# MCU.net
KiCad netlist of a schematic drawn in Altium Designer
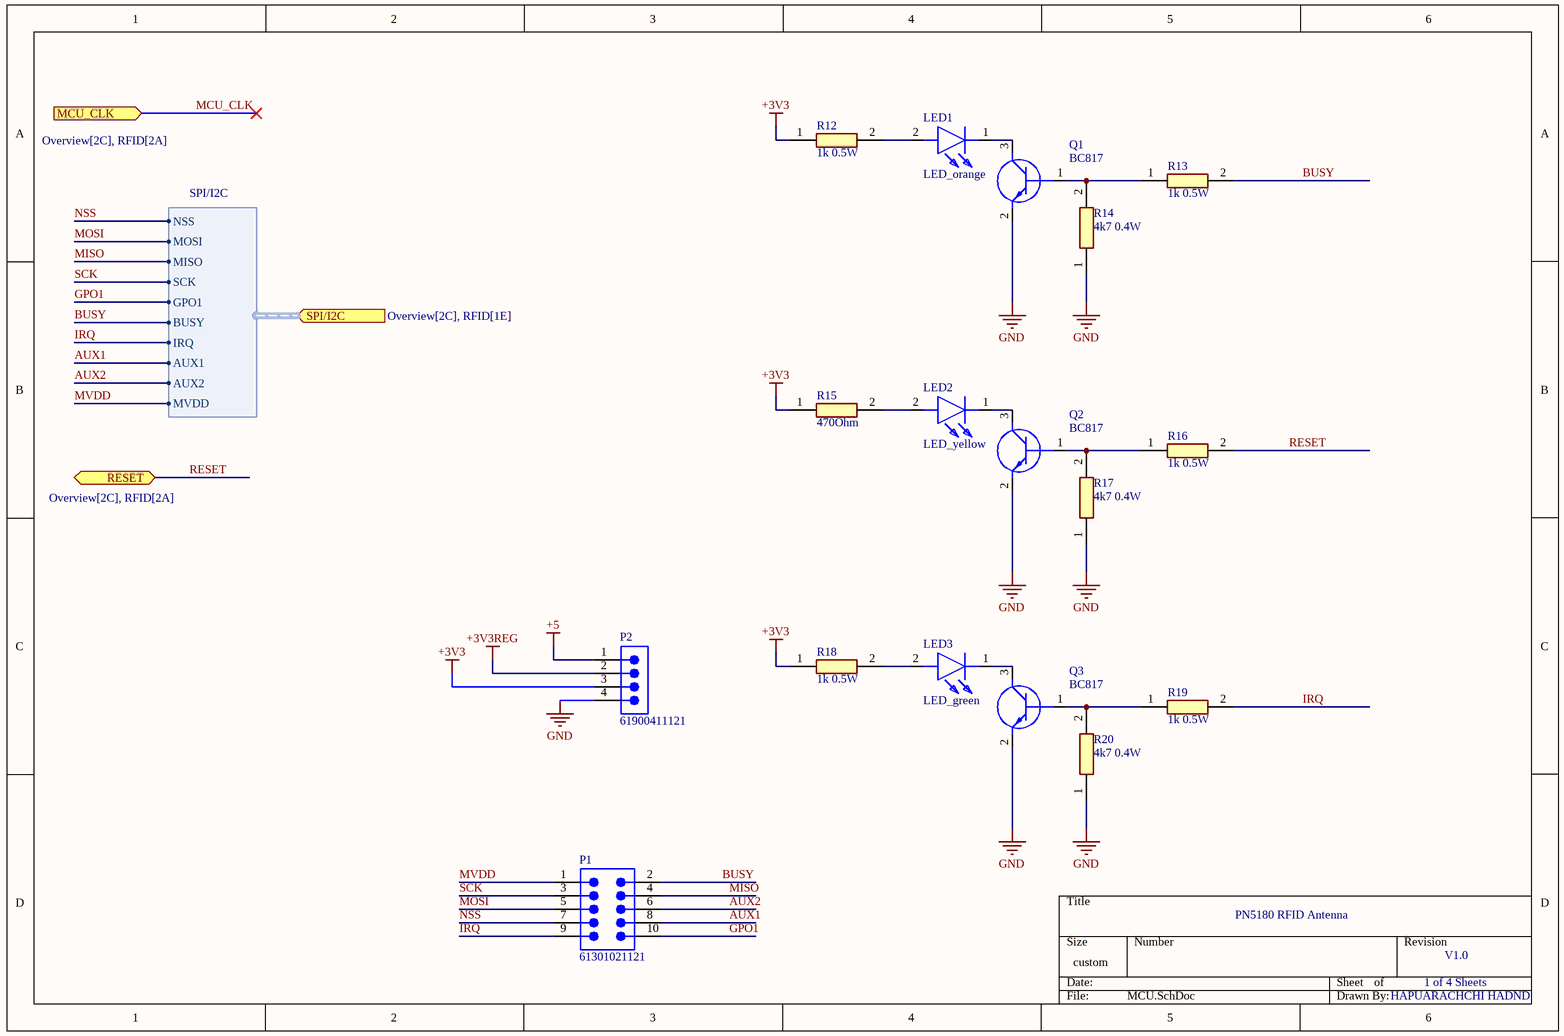
[diagram p0: MCU.SchDoc]

(export (version "E")
  (design (tool "Eeschema 10.0.6"))
  (components
    (comp (ref "LED1")
      (value "LED_orange")
      (footprint "Antenna_Order:LEDC3216X120N")
      (description "LED")
      (fields
        (field (name "MANUFACTURER_PART_NUMBER") "LTST-C150KAKT")
        (field (name "MOUSER PART NUMBER") "859-LTST-C150KAKT")
      )
      (libsource (lib "Antenna_Order") (part "LED_orange"))
    )
    (comp (ref "LED2")
      (value "LED_yellow")
      (footprint "Antenna_Order:LTSTC171KSKT")
      (description "LED")
      (fields
        (field (name "MANUFACTURER_PART_NUMBER") "LTST-C171KSKT")
        (field (name "MOUSER PART NUMBER") "859-LTST-C171KSKT")
      )
      (libsource (lib "Antenna_Order") (part "LED_yellow"))
    )
    (comp (ref "LED3")
      (value "LED_green")
      (footprint "Antenna_Order:LEDC2012X90N")
      (description "LED")
      (fields
        (field (name "MANUFACTURER_PART_NUMBER") "LTST-C171KGKT")
        (field (name "MOUSER PART NUMBER") "859-LTST-C171KGKT")
      )
      (libsource (lib "Antenna_Order") (part "LED_green"))
    )
    (comp (ref "P1")
      (value "61301021121")
      (footprint "61301021121")
      (libsource (lib "Altium Content Vault") (part "Header_Male_2R_10P"))
    )
    (comp (ref "P2")
      (value "61900411121")
      (footprint "61900411121")
      (libsource (lib "Altium Content Vault") (part "Header_Male_1R_04P"))
    )
    (comp (ref "Q1")
      (value "BC817")
      (footprint "Antenna_Order:SOT96P237X111-3N")
      (description "Bipolar (BJT) Transistor NPN 80 V 500 mA 100MHz 225 mW Surface Mount SOT-23-3 (TO-236)")
      (fields
        (field (name "MANUFACTURER_PART_NUMBER") "SMMBTA06LT3G")
        (field (name "MOUSER PART NUMBER") "863-SMMBTA06LT3G")
      )
      (libsource (lib "Antenna_Order") (part "BC817"))
    )
    (comp (ref "Q2")
      (value "BC817")
      (footprint "Antenna_Order:SOT96P237X111-3N")
      (description "Bipolar (BJT) Transistor NPN 80 V 500 mA 100MHz 225 mW Surface Mount SOT-23-3 (TO-236)")
      (fields
        (field (name "MANUFACTURER_PART_NUMBER") "SMMBTA06LT3G")
        (field (name "MOUSER PART NUMBER") "863-SMMBTA06LT3G")
      )
      (libsource (lib "Antenna_Order") (part "BC817"))
    )
    (comp (ref "Q3")
      (value "BC817")
      (footprint "Antenna_Order:SOT96P237X111-3N")
      (description "Bipolar (BJT) Transistor NPN 80 V 500 mA 100MHz 225 mW Surface Mount SOT-23-3 (TO-236)")
      (fields
        (field (name "MANUFACTURER_PART_NUMBER") "SMMBTA06LT3G")
        (field (name "MOUSER PART NUMBER") "863-SMMBTA06LT3G")
      )
      (libsource (lib "Antenna_Order") (part "BC817"))
    )
    (comp (ref "R12")
      (value "1k 0.5W")
      (footprint "Antenna_Order:RESC1608X58N")
      (description "1 kOhms ±0.1% 0.5W, 1/2W Chip Resistor 0603 (1608 Metric) Thin Film")
      (fields
        (field (name "MANUFACTURER_PART_NUMBER") "RA73F1J1K0BTDF")
        (field (name "MOUSER PART NUMBER") "279-RA73F1J1K0BTDF")
      )
      (libsource (lib "Antenna_Order") (part "1kOhm"))
    )
    (comp (ref "R13")
      (value "1k 0.5W")
      (footprint "Antenna_Order:RESC1608X58N")
      (description "1 kOhms ±0.1% 0.5W, 1/2W Chip Resistor 0603 (1608 Metric) Thin Film")
      (fields
        (field (name "MANUFACTURER_PART_NUMBER") "RA73F1J1K0BTDF")
        (field (name "MOUSER PART NUMBER") "279-RA73F1J1K0BTDF")
      )
      (libsource (lib "Antenna_Order") (part "1kOhm"))
    )
    (comp (ref "R14")
      (value "4k7 0.4W")
      (footprint "Antenna_Order:RESC1608X55N_1")
      (fields
        (field (name "MANUFACTURER_PART_NUMBER") "SDR03EZPF4701")
        (field (name "MOUSER PART NUMBER") "755-SDR03EZPF4701")
      )
      (libsource (lib "Antenna_Order") (part "4k7Ohm_0603"))
    )
    (comp (ref "R15")
      (value "470Ohm")
      (footprint "Antenna_Order:RESC1608X55N")
      (description "SMD 0603 470ohm 1% Anti Surge AEC-Q200")
      (fields
        (field (name "MANUFACTURER_PART_NUMBER") "ESR03EZPF4700")
        (field (name "MOUSER PART NUMBER") "755-ESR03EZPF4700")
      )
      (libsource (lib "Antenna_Order") (part "470Ohm"))
    )
    (comp (ref "R16")
      (value "1k 0.5W")
      (footprint "Antenna_Order:RESC1608X58N")
      (description "1 kOhms ±0.1% 0.5W, 1/2W Chip Resistor 0603 (1608 Metric) Thin Film")
      (fields
        (field (name "MANUFACTURER_PART_NUMBER") "RA73F1J1K0BTDF")
        (field (name "MOUSER PART NUMBER") "279-RA73F1J1K0BTDF")
      )
      (libsource (lib "Antenna_Order") (part "1kOhm"))
    )
    (comp (ref "R17")
      (value "4k7 0.4W")
      (footprint "Antenna_Order:RESC1608X55N_1")
      (fields
        (field (name "MANUFACTURER_PART_NUMBER") "SDR03EZPF4701")
        (field (name "MOUSER PART NUMBER") "755-SDR03EZPF4701")
      )
      (libsource (lib "Antenna_Order") (part "4k7Ohm_0603"))
    )
    (comp (ref "R18")
      (value "1k 0.5W")
      (footprint "Antenna_Order:RESC1608X58N")
      (description "1 kOhms ±0.1% 0.5W, 1/2W Chip Resistor 0603 (1608 Metric) Thin Film")
      (fields
        (field (name "MANUFACTURER_PART_NUMBER") "RA73F1J1K0BTDF")
        (field (name "MOUSER PART NUMBER") "279-RA73F1J1K0BTDF")
      )
      (libsource (lib "Antenna_Order") (part "1kOhm"))
    )
    (comp (ref "R19")
      (value "1k 0.5W")
      (footprint "Antenna_Order:RESC1608X58N")
      (description "1 kOhms ±0.1% 0.5W, 1/2W Chip Resistor 0603 (1608 Metric) Thin Film")
      (fields
        (field (name "MANUFACTURER_PART_NUMBER") "RA73F1J1K0BTDF")
        (field (name "MOUSER PART NUMBER") "279-RA73F1J1K0BTDF")
      )
      (libsource (lib "Antenna_Order") (part "1kOhm"))
    )
    (comp (ref "R20")
      (value "4k7 0.4W")
      (footprint "Antenna_Order:RESC1608X55N_1")
      (fields
        (field (name "MANUFACTURER_PART_NUMBER") "SDR03EZPF4701")
        (field (name "MOUSER PART NUMBER") "755-SDR03EZPF4701")
      )
      (libsource (lib "Antenna_Order") (part "4k7Ohm_0603"))
    )
  )
  (nets
    (net (code "2") (name "+3V3") (class "Default")
      (node (ref "P2") (pin "3") (pinfunction "3_3") (pintype "passive"))
      (node (ref "R12") (pin "1") (pinfunction "1_1") (pintype "passive"))
      (node (ref "R15") (pin "1") (pinfunction "1_1") (pintype "passive"))
      (node (ref "R18") (pin "1") (pinfunction "1_1") (pintype "passive"))
    )
    (net (code "3") (name "+3V3REG") (class "Default")
      (node (ref "P2") (pin "2") (pinfunction "2_2") (pintype "passive"))
    )
    (net (code "4") (name "+5") (class "Default")
      (node (ref "P2") (pin "1") (pinfunction "1_1") (pintype "passive"))
    )
    (net (code "5") (name "/AUX1") (class "Default")
      (node (ref "P1") (pin "8") (pinfunction "8_8") (pintype "passive"))
    )
    (net (code "6") (name "/AUX2") (class "Default")
      (node (ref "P1") (pin "6") (pinfunction "6_6") (pintype "passive"))
    )
    (net (code "7") (name "/BUSY") (class "Default")
      (node (ref "P1") (pin "2") (pinfunction "2_2") (pintype "passive"))
      (node (ref "R13") (pin "2") (pinfunction "2_2") (pintype "passive"))
    )
    (net (code "8") (name "/GPO1") (class "Default")
      (node (ref "P1") (pin "10") (pinfunction "10_10") (pintype "passive"))
    )
    (net (code "9") (name "/IRQ") (class "Default")
      (node (ref "P1") (pin "9") (pinfunction "9_9") (pintype "passive"))
      (node (ref "R19") (pin "2") (pinfunction "2_2") (pintype "passive"))
    )
    (net (code "11") (name "/MISO") (class "Default")
      (node (ref "P1") (pin "4") (pinfunction "4_4") (pintype "passive"))
    )
    (net (code "12") (name "/MOSI") (class "Default")
      (node (ref "P1") (pin "5") (pinfunction "5_5") (pintype "passive"))
    )
    (net (code "13") (name "/MVDD") (class "Default")
      (node (ref "P1") (pin "1") (pinfunction "1_1") (pintype "passive"))
    )
    (net (code "14") (name "/NSS") (class "Default")
      (node (ref "P1") (pin "7") (pinfunction "7_7") (pintype "passive"))
    )
    (net (code "15") (name "/RESET") (class "Default")
      (node (ref "R16") (pin "2") (pinfunction "2_2") (pintype "passive"))
    )
    (net (code "16") (name "/SCK") (class "Default")
      (node (ref "P1") (pin "3") (pinfunction "3_3") (pintype "passive"))
    )
    (net (code "18") (name "GND") (class "Default")
      (node (ref "P2") (pin "4") (pinfunction "4_4") (pintype "passive"))
      (node (ref "Q1") (pin "2") (pinfunction "E_2") (pintype "passive"))
      (node (ref "Q2") (pin "2") (pinfunction "E_2") (pintype "passive"))
      (node (ref "Q3") (pin "2") (pinfunction "E_2") (pintype "passive"))
      (node (ref "R14") (pin "1") (pinfunction "1_1") (pintype "passive"))
      (node (ref "R17") (pin "1") (pinfunction "1_1") (pintype "passive"))
      (node (ref "R20") (pin "1") (pinfunction "1_1") (pintype "passive"))
    )
    (net (code "19") (name "Net-(LED1-A)") (class "Default")
      (node (ref "LED1") (pin "2") (pinfunction "A_2") (pintype "passive"))
      (node (ref "R12") (pin "2") (pinfunction "2_2") (pintype "passive"))
    )
    (net (code "20") (name "Net-(LED1-K)") (class "Default")
      (node (ref "LED1") (pin "1") (pinfunction "K_1") (pintype "passive"))
      (node (ref "Q1") (pin "3") (pinfunction "C_3") (pintype "passive"))
    )
    (net (code "21") (name "Net-(LED2-A)") (class "Default")
      (node (ref "LED2") (pin "2") (pinfunction "A_2") (pintype "passive"))
      (node (ref "R15") (pin "2") (pinfunction "2_2") (pintype "passive"))
    )
    (net (code "22") (name "Net-(LED2-K)") (class "Default")
      (node (ref "LED2") (pin "1") (pinfunction "K_1") (pintype "passive"))
      (node (ref "Q2") (pin "3") (pinfunction "C_3") (pintype "passive"))
    )
    (net (code "23") (name "Net-(LED3-A)") (class "Default")
      (node (ref "LED3") (pin "2") (pinfunction "A_2") (pintype "passive"))
      (node (ref "R18") (pin "2") (pinfunction "2_2") (pintype "passive"))
    )
    (net (code "24") (name "Net-(LED3-K)") (class "Default")
      (node (ref "LED3") (pin "1") (pinfunction "K_1") (pintype "passive"))
      (node (ref "Q3") (pin "3") (pinfunction "C_3") (pintype "passive"))
    )
    (net (code "25") (name "Net-(Q1-B)") (class "Default")
      (node (ref "Q1") (pin "1") (pinfunction "B_1") (pintype "passive"))
      (node (ref "R13") (pin "1") (pinfunction "1_1") (pintype "passive"))
      (node (ref "R14") (pin "2") (pinfunction "2_2") (pintype "passive"))
    )
    (net (code "26") (name "Net-(Q2-B)") (class "Default")
      (node (ref "Q2") (pin "1") (pinfunction "B_1") (pintype "passive"))
      (node (ref "R16") (pin "1") (pinfunction "1_1") (pintype "passive"))
      (node (ref "R17") (pin "2") (pinfunction "2_2") (pintype "passive"))
    )
    (net (code "27") (name "Net-(Q3-B)") (class "Default")
      (node (ref "Q3") (pin "1") (pinfunction "B_1") (pintype "passive"))
      (node (ref "R19") (pin "1") (pinfunction "1_1") (pintype "passive"))
      (node (ref "R20") (pin "2") (pinfunction "2_2") (pintype "passive"))
    )
  )
)
